# Ethernet.net
KiCad netlist of a schematic drawn in Altium Designer
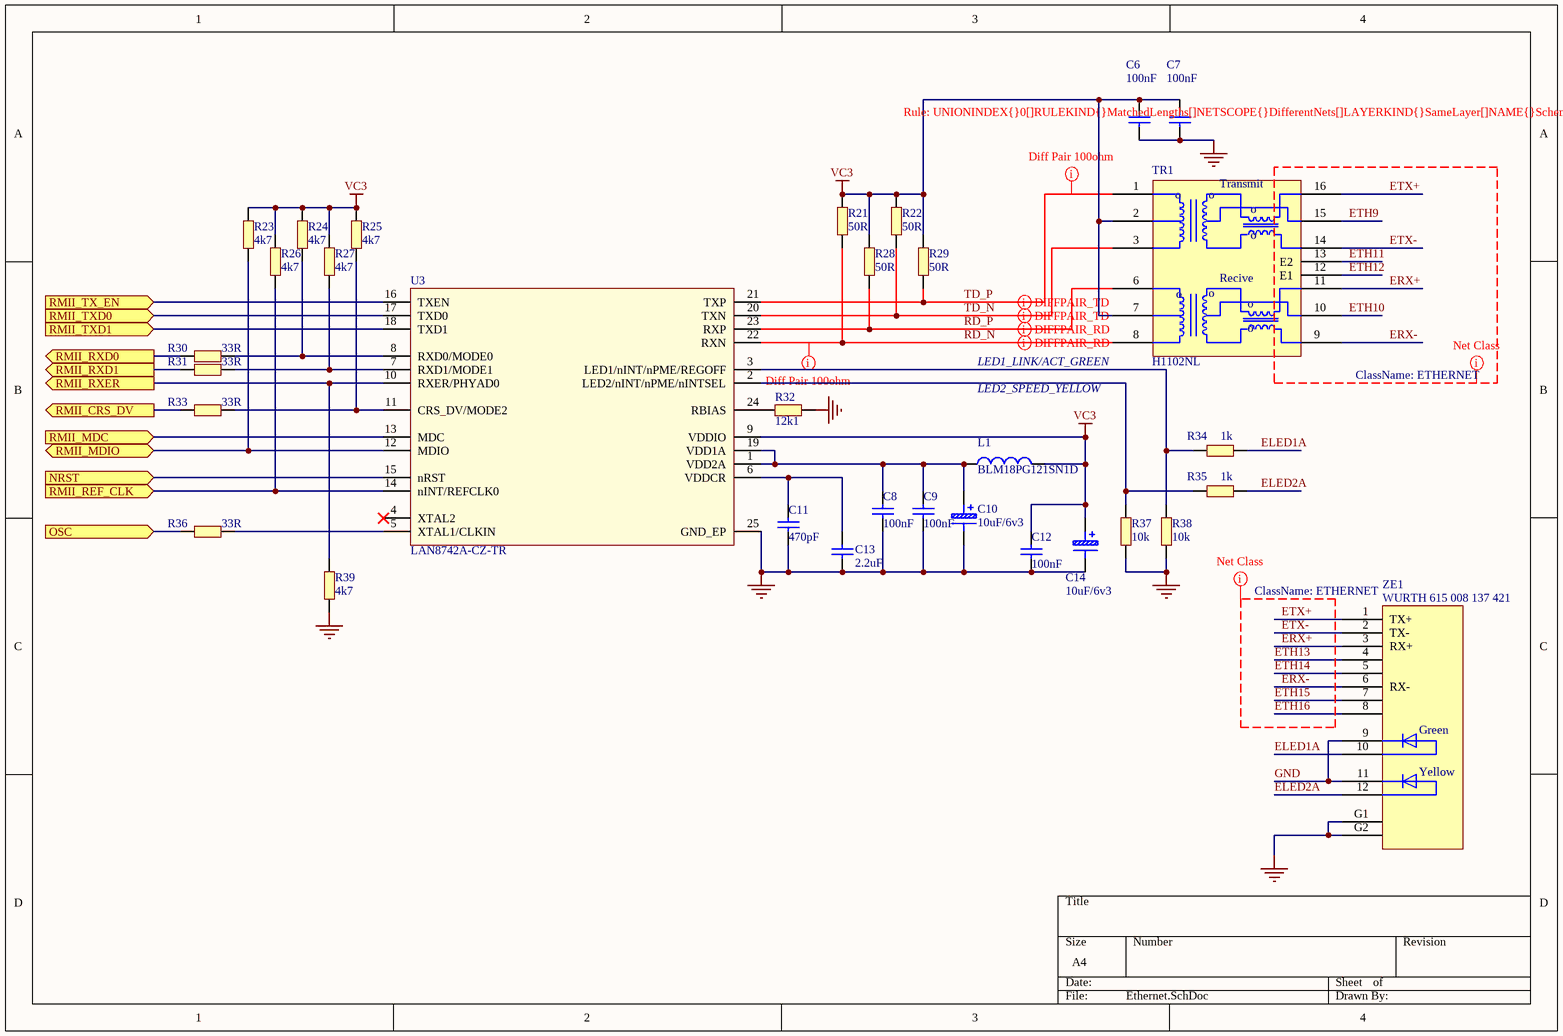
[diagram p0: Ethernet.SchDoc]

(export (version "E")
  (design (tool "Eeschema 10.0.6"))
  (components
    (comp (ref "C6")
      (value "100nF")
      (footprint "0805C")
      (description "Capacitor,100nF,16V,X7R,10%,0402,YAGEO")
      (libsource (lib "MCD_TOOLS") (part "Cap_100nF_X7R_10%_0402"))
    )
    (comp (ref "C7")
      (value "100nF")
      (footprint "0805C")
      (description "Capacitor,100nF,16V,X7R,10%,0402,YAGEO")
      (libsource (lib "MCD_TOOLS") (part "Cap_100nF_X7R_10%_0402"))
    )
    (comp (ref "C8")
      (value "100nF")
      (footprint "0805C")
      (description "Capacitor,100nF,16V,X7R,10%,0402,YAGEO")
      (libsource (lib "MCD_TOOLS") (part "Cap_100nF_X7R_10%_0402"))
    )
    (comp (ref "C9")
      (value "100nF")
      (footprint "0805C")
      (description "Capacitor,100nF,16V,X7R,10%,0402,YAGEO")
      (libsource (lib "MCD_TOOLS") (part "Cap_100nF_X7R_10%_0402"))
    )
    (comp (ref "C10") (value "10uF/6v3") (footprint "CAP_A") (libsource (lib "GkSchlib") (part "CapTantal")))
    (comp (ref "C11")
      (value "470pF")
      (footprint "0805C")
      (description "Capacitor,470pF,16V,X7R,10%,0402,YAGEO")
      (libsource (lib "MCD_TOOLS") (part "Cap_470pF_X7R_10%_0402"))
    )
    (comp (ref "C12")
      (value "100nF")
      (footprint "0805C")
      (description "Capacitor,100nF,16V,X7R,10%,0402,YAGEO")
      (libsource (lib "MCD_TOOLS") (part "Cap_100nF_X7R_10%_0402"))
    )
    (comp (ref "C13")
      (value "2.2uF")
      (footprint "0805C")
      (description "Capacitor,1uF,16V,X5R,10%,0603,YAGEO")
      (libsource (lib "MCD_TOOLS") (part "Cap_1uF_X5R_10%_0603"))
    )
    (comp (ref "C14") (value "10uF/6v3") (footprint "CAP_A") (libsource (lib "GkSchlib") (part "CapTantal")))
    (comp (ref "L1")
      (value "BLM18PG121SN1D")
      (footprint "0805")
      (description "Bead,120R,2A,0603,BLM18PG121SN1D,MURATA")
      (libsource (lib "MCD_TOOLS") (part "BEAD_120R_2A_0603"))
    )
    (comp (ref "R21") (value "50R") (footprint "0805R") (libsource (lib "") (part "RES3_1")))
    (comp (ref "R22") (value "50R") (footprint "0805R") (libsource (lib "") (part "RES3_1")))
    (comp (ref "R23") (value "4k7") (footprint "0805R") (libsource (lib "") (part "RES3_1")))
    (comp (ref "R24") (value "4k7") (footprint "0805R") (libsource (lib "") (part "RES3_1")))
    (comp (ref "R25") (value "4k7") (footprint "0805R") (libsource (lib "") (part "RES3_1")))
    (comp (ref "R26") (value "4k7") (footprint "0805R") (libsource (lib "") (part "RES3_1")))
    (comp (ref "R27") (value "4k7") (footprint "0805R") (libsource (lib "") (part "RES3_1")))
    (comp (ref "R28") (value "50R") (footprint "0805R") (libsource (lib "") (part "RES3_1")))
    (comp (ref "R29") (value "50R") (footprint "0805R") (libsource (lib "") (part "RES3_1")))
    (comp (ref "R30") (value "33R") (footprint "0805R") (libsource (lib "*") (part "RES3")))
    (comp (ref "R31") (value "33R") (footprint "0805R") (libsource (lib "*") (part "RES3")))
    (comp (ref "R32") (value "12k1") (footprint "0805R") (libsource (lib "") (part "RES3_2")))
    (comp (ref "R33") (value "33R") (footprint "0805R") (libsource (lib "*") (part "RES3")))
    (comp (ref "R34") (value "1k") (footprint "0805R") (libsource (lib "") (part "RES3_2")))
    (comp (ref "R35") (value "1k") (footprint "0805R") (libsource (lib "") (part "RES3_2")))
    (comp (ref "R36") (value "33R") (footprint "0805R") (libsource (lib "*") (part "RES3")))
    (comp (ref "R37") (value "10k") (footprint "0805R") (libsource (lib "") (part "RES3_1")))
    (comp (ref "R38") (value "10k") (footprint "0805R") (libsource (lib "") (part "RES3_1")))
    (comp (ref "R39") (value "4k7") (footprint "0805R") (libsource (lib "") (part "RES3_1")))
    (comp (ref "TR1") (value "H1102NL") (footprint "H1102") (libsource (lib "GkSchlib") (part "H1102NL")))
    (comp (ref "U3")
      (value "LAN8742A-CZ-TR")
      (footprint "QFN24_LAN")
      (libsource (lib "MCD_TOOLS") (part "LAN8742A-CZ-TR"))
    )
    (comp (ref "ZE1")
      (value "WURTH 615 008 137 421")
      (footprint "RJ45GELED")
      (libsource (lib "*") (part "RJ45GELED"))
    )
  )
  (nets
    (net (code "1") (name "/ELED1A") (class "Default")
      (node (ref "R34") (pin "1") (pintype "passive"))
      (node (ref "ZE1") (pin "10") (pintype "passive"))
    )
    (net (code "2") (name "/ELED2A") (class "Default")
      (node (ref "R35") (pin "1") (pintype "passive"))
      (node (ref "ZE1") (pin "12") (pintype "passive"))
    )
    (net (code "3") (name "/ERX+") (class "Default")
      (node (ref "TR1") (pin "11") (pinfunction "RO1_11") (pintype "passive"))
      (node (ref "ZE1") (pin "3") (pinfunction "RX+_3") (pintype "passive"))
    )
    (net (code "4") (name "/ERX-") (class "Default")
      (node (ref "TR1") (pin "9") (pinfunction "RO2_9") (pintype "passive"))
      (node (ref "ZE1") (pin "6") (pinfunction "RX-_6") (pintype "passive"))
    )
    (net (code "5") (name "/ETH9") (class "Default") (node (ref "TR1") (pin "15") (pintype "passive")))
    (net (code "6") (name "/ETH10") (class "Default") (node (ref "TR1") (pin "10") (pintype "passive")))
    (net (code "7") (name "/ETH11") (class "Default")
      (node (ref "TR1") (pin "13") (pinfunction "E2_13") (pintype "passive"))
    )
    (net (code "8") (name "/ETH12") (class "Default")
      (node (ref "TR1") (pin "12") (pinfunction "E1_12") (pintype "passive"))
    )
    (net (code "9") (name "/ETH13") (class "Default") (node (ref "ZE1") (pin "4") (pintype "passive")))
    (net (code "10") (name "/ETH14") (class "Default") (node (ref "ZE1") (pin "5") (pintype "passive")))
    (net (code "11") (name "/ETH15") (class "Default") (node (ref "ZE1") (pin "7") (pintype "passive")))
    (net (code "12") (name "/ETH16") (class "Default") (node (ref "ZE1") (pin "8") (pintype "passive")))
    (net (code "13") (name "/ETX+") (class "Default")
      (node (ref "TR1") (pin "16") (pinfunction "TO1_16") (pintype "passive"))
      (node (ref "ZE1") (pin "1") (pinfunction "TX+_1") (pintype "passive"))
    )
    (net (code "14") (name "/ETX-") (class "Default")
      (node (ref "TR1") (pin "14") (pinfunction "TO2_14") (pintype "passive"))
      (node (ref "ZE1") (pin "2") (pinfunction "TX-_2") (pintype "passive"))
    )
    (net (code "15") (name "/NRST") (class "Default")
      (node (ref "U3") (pin "15") (pinfunction "nRST_15") (pintype "passive"))
    )
    (net (code "16") (name "/OSC") (class "Default") (node (ref "R36") (pin "1") (pintype "passive")))
    (net (code "17") (name "/RD_N") (class "Default")
      (node (ref "R21") (pin "1") (pintype "passive"))
      (node (ref "TR1") (pin "8") (pinfunction "RI3_8") (pintype "passive"))
      (node (ref "U3") (pin "22") (pinfunction "RXN_22") (pintype "passive"))
    )
    (net (code "18") (name "/RD_P") (class "Default")
      (node (ref "R28") (pin "1") (pintype "passive"))
      (node (ref "TR1") (pin "6") (pinfunction "RI1_6") (pintype "passive"))
      (node (ref "U3") (pin "23") (pinfunction "RXP_23") (pintype "passive"))
    )
    (net (code "19") (name "/RMII_CRS_DV") (class "Default") (node (ref "R33") (pin "1") (pintype "passive")))
    (net (code "20") (name "/RMII_MDC") (class "Default")
      (node (ref "U3") (pin "13") (pinfunction "MDC_13") (pintype "passive"))
    )
    (net (code "21") (name "/RMII_MDIO") (class "Default")
      (node (ref "R23") (pin "1") (pintype "passive"))
      (node (ref "U3") (pin "12") (pinfunction "MDIO_12") (pintype "passive"))
    )
    (net (code "22") (name "/RMII_REF_CLK") (class "Default")
      (node (ref "R26") (pin "1") (pintype "passive"))
      (node (ref "U3") (pin "14") (pinfunction "nINT/REFCLK0_14") (pintype "passive"))
    )
    (net (code "23") (name "/RMII_RXD0") (class "Default") (node (ref "R30") (pin "1") (pintype "passive")))
    (net (code "24") (name "/RMII_RXD1") (class "Default") (node (ref "R31") (pin "1") (pintype "passive")))
    (net (code "25") (name "/RMII_RXER") (class "Default")
      (node (ref "R39") (pin "2") (pintype "passive"))
      (node (ref "U3") (pin "10") (pinfunction "RXER/PHYAD0_10") (pintype "passive"))
    )
    (net (code "26") (name "/RMII_TXD0") (class "Default")
      (node (ref "U3") (pin "17") (pinfunction "TXD0_17") (pintype "passive"))
    )
    (net (code "27") (name "/RMII_TXD1") (class "Default")
      (node (ref "U3") (pin "18") (pinfunction "TXD1_18") (pintype "passive"))
    )
    (net (code "28") (name "/RMII_TX_EN") (class "Default")
      (node (ref "U3") (pin "16") (pinfunction "TXEN_16") (pintype "passive"))
    )
    (net (code "29") (name "/TD_N") (class "Default")
      (node (ref "R22") (pin "1") (pintype "passive"))
      (node (ref "TR1") (pin "3") (pinfunction "TI3_3") (pintype "passive"))
      (node (ref "U3") (pin "20") (pinfunction "TXN_20") (pintype "passive"))
    )
    (net (code "30") (name "/TD_P") (class "Default")
      (node (ref "R29") (pin "1") (pintype "passive"))
      (node (ref "TR1") (pin "1") (pinfunction "TI1_1") (pintype "passive"))
      (node (ref "U3") (pin "21") (pinfunction "TXP_21") (pintype "passive"))
    )
    (net (code "31") (name "GND") (class "Default")
      (node (ref "C10") (pin "1") (pintype "passive"))
      (node (ref "C11") (pin "1") (pinfunction "1_1") (pintype "passive"))
      (node (ref "C12") (pin "1") (pinfunction "1_1") (pintype "passive"))
      (node (ref "C13") (pin "1") (pinfunction "1_1") (pintype "passive"))
      (node (ref "C14") (pin "1") (pintype "passive"))
      (node (ref "C6") (pin "1") (pinfunction "1_1") (pintype "passive"))
      (node (ref "C7") (pin "1") (pinfunction "1_1") (pintype "passive"))
      (node (ref "C8") (pin "1") (pinfunction "1_1") (pintype "passive"))
      (node (ref "C9") (pin "1") (pinfunction "1_1") (pintype "passive"))
      (node (ref "R32") (pin "1") (pintype "passive"))
      (node (ref "R37") (pin "1") (pintype "passive"))
      (node (ref "R38") (pin "1") (pintype "passive"))
      (node (ref "R39") (pin "1") (pintype "passive"))
      (node (ref "U3") (pin "25") (pinfunction "GND_EP_25") (pintype "passive"))
      (node (ref "ZE1") (pin "11") (pintype "passive"))
      (node (ref "ZE1") (pin "9") (pintype "passive"))
      (node (ref "ZE1") (pin "G1") (pintype "passive"))
      (node (ref "ZE1") (pin "G2") (pintype "passive"))
    )
    (net (code "32") (name "Net-(U3-CRS_DV{slash}MODE2)") (class "Default")
      (node (ref "R25") (pin "1") (pintype "passive"))
      (node (ref "R33") (pin "2") (pintype "passive"))
      (node (ref "U3") (pin "11") (pinfunction "CRS_DV/MODE2_11") (pintype "passive"))
    )
    (net (code "33") (name "Net-(U3-LED1{slash}nINT{slash}nPME{slash}REGOFF)") (class "Default")
      (node (ref "R34") (pin "2") (pintype "passive"))
      (node (ref "R38") (pin "2") (pintype "passive"))
      (node (ref "U3") (pin "3") (pinfunction "LED1/nINT/nPME/REGOFF_3") (pintype "passive"))
    )
    (net (code "34") (name "Net-(U3-LED2{slash}nINT{slash}nPME{slash}nINTSEL)") (class "Default")
      (node (ref "R35") (pin "2") (pintype "passive"))
      (node (ref "R37") (pin "2") (pintype "passive"))
      (node (ref "U3") (pin "2") (pinfunction "LED2/nINT/nPME/nINTSEL_2") (pintype "passive"))
    )
    (net (code "35") (name "Net-(U3-RBIAS)") (class "Default")
      (node (ref "R32") (pin "2") (pintype "passive"))
      (node (ref "U3") (pin "24") (pinfunction "RBIAS_24") (pintype "passive"))
    )
    (net (code "36") (name "Net-(U3-RXD0{slash}MODE0)") (class "Default")
      (node (ref "R24") (pin "1") (pintype "passive"))
      (node (ref "R30") (pin "2") (pintype "passive"))
      (node (ref "U3") (pin "8") (pinfunction "RXD0/MODE0_8") (pintype "passive"))
    )
    (net (code "37") (name "Net-(U3-RXD1{slash}MODE1)") (class "Default")
      (node (ref "R27") (pin "1") (pintype "passive"))
      (node (ref "R31") (pin "2") (pintype "passive"))
      (node (ref "U3") (pin "7") (pinfunction "RXD1/MODE1_7") (pintype "passive"))
    )
    (net (code "38") (name "Net-(U3-VDD1A)") (class "Default")
      (node (ref "C10") (pin "2") (pintype "passive"))
      (node (ref "C8") (pin "2") (pinfunction "2_2") (pintype "passive"))
      (node (ref "C9") (pin "2") (pinfunction "2_2") (pintype "passive"))
      (node (ref "L1") (pin "1") (pinfunction "1_1") (pintype "passive"))
      (node (ref "U3") (pin "1") (pinfunction "VDD2A_1") (pintype "passive"))
      (node (ref "U3") (pin "19") (pinfunction "VDD1A_19") (pintype "passive"))
    )
    (net (code "39") (name "Net-(U3-VDDCR)") (class "Default")
      (node (ref "C11") (pin "2") (pinfunction "2_2") (pintype "passive"))
      (node (ref "C13") (pin "2") (pinfunction "2_2") (pintype "passive"))
      (node (ref "U3") (pin "6") (pinfunction "VDDCR_6") (pintype "passive"))
    )
    (net (code "40") (name "Net-(U3-XTAL1{slash}CLKIN)") (class "Default")
      (node (ref "R36") (pin "2") (pintype "passive"))
      (node (ref "U3") (pin "5") (pinfunction "XTAL1/CLKIN_5") (pintype "passive"))
    )
    (net (code "41") (name "VC3") (class "Default")
      (node (ref "C12") (pin "2") (pinfunction "2_2") (pintype "passive"))
      (node (ref "C14") (pin "2") (pintype "passive"))
      (node (ref "C6") (pin "2") (pinfunction "2_2") (pintype "passive"))
      (node (ref "C7") (pin "2") (pinfunction "2_2") (pintype "passive"))
      (node (ref "L1") (pin "2") (pinfunction "2_2") (pintype "passive"))
      (node (ref "R21") (pin "2") (pintype "passive"))
      (node (ref "R22") (pin "2") (pintype "passive"))
      (node (ref "R23") (pin "2") (pintype "passive"))
      (node (ref "R24") (pin "2") (pintype "passive"))
      (node (ref "R25") (pin "2") (pintype "passive"))
      (node (ref "R26") (pin "2") (pintype "passive"))
      (node (ref "R27") (pin "2") (pintype "passive"))
      (node (ref "R28") (pin "2") (pintype "passive"))
      (node (ref "R29") (pin "2") (pintype "passive"))
      (node (ref "TR1") (pin "2") (pinfunction "TI2_2") (pintype "passive"))
      (node (ref "TR1") (pin "7") (pinfunction "RI2_7") (pintype "passive"))
      (node (ref "U3") (pin "9") (pinfunction "VDDIO_9") (pintype "passive"))
    )
    (net (code "42") (name "unconnected-(U3-XTAL2-Pad4)") (class "Default")
      (node (ref "U3") (pin "4") (pinfunction "XTAL2_4") (pintype "passive+no_connect"))
    )
  )
)
